# child2.net
KiCad netlist of a schematic drawn in Altium Designer
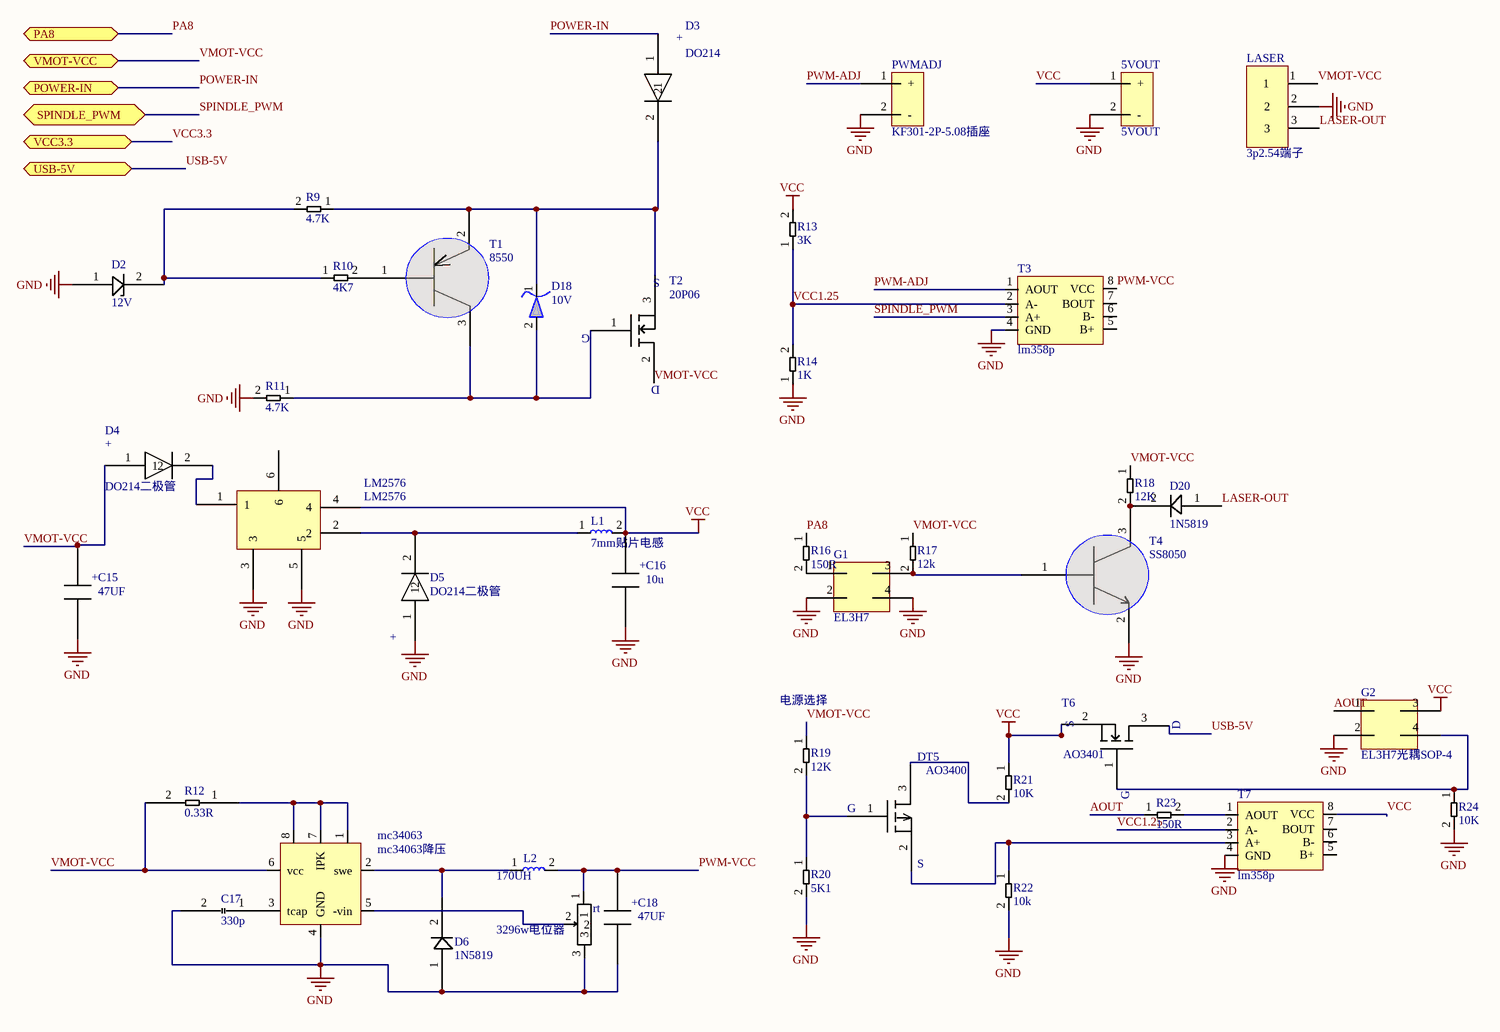
[diagram p0: child2.SchDoc]

(export (version "E")
  (design (tool "Eeschema 10.0.6"))
  (components
    (comp (ref "5VOUT")
      (value "5VOUT")
      (footprint "KF301-2P-5.08插座")
      (libsource (lib "51单片机") (part "KF301-2P-5.08插座"))
    )
    (comp (ref "C15") (value "47UF") (footprint "10u电解电容") (libsource (lib "51单片机") (part "10u电解电容")))
    (comp (ref "C16") (value "10u") (footprint "10u电解电容") (libsource (lib "51单片机") (part "10u电解电容")))
    (comp (ref "C17") (value "330p") (footprint "0805电容") (libsource (lib "51单片机") (part "0805贴片电容")))
    (comp (ref "C18") (value "47UF") (footprint "10u电解电容") (libsource (lib "51单片机") (part "10u电解电容")))
    (comp (ref "D2") (value "12V") (footprint "稳压二极管30v") (libsource (lib "51单片机") (part "稳压二极管")))
    (comp (ref "D3") (value "DO214") (footprint "SMA封装二极管") (libsource (lib "51单片机") (part "DO214二极管")))
    (comp (ref "D4") (value "DO214二极管") (footprint "SMA封装二极管") (libsource (lib "51单片机") (part "DO214二极管")))
    (comp (ref "D5") (value "DO214二极管") (footprint "SMA封装二极管") (libsource (lib "51单片机") (part "DO214二极管")))
    (comp (ref "D6") (value "1N5819") (footprint "0805-二极管") (libsource (lib "51单片机") (part "0805二极管")))
    (comp (ref "D18") (value "10V") (footprint "1/2w贴片稳压二极管") (libsource (lib "51单片机") (part "贴片稳压二极管")))
    (comp (ref "D20") (value "1N5819") (footprint "0805-二极管") (libsource (lib "51单片机") (part "0805二极管")))
    (comp (ref "G1") (value "EL3H7") (footprint "EL3H7SOP-4") (libsource (lib "51单片机") (part "EL3H7光耦SOP-4")))
    (comp (ref "G2")
      (value "EL3H7光耦SOP-4")
      (footprint "EL3H7SOP-4")
      (libsource (lib "51单片机") (part "EL3H7光耦SOP-4"))
    )
    (comp (ref "L1") (value "7mm贴片电感") (footprint "7MM贴片电感") (libsource (lib "51单片机") (part "7mm贴片电感")))
    (comp (ref "L2") (value "170UH") (footprint "7MM贴片电感") (libsource (lib "51单片机") (part "7mm贴片电感")))
    (comp (ref "LASER") (value "3p2.54端子") (footprint "3p2.54端子") (libsource (lib "51单片机") (part "3p2.54端子")))
    (comp (ref "LM2576") (value "LM2576") (footprint "LM2576") (libsource (lib "51单片机") (part "LM2576")))
    (comp (ref "mc34063")
      (value "mc34063降压")
      (footprint "SOP-8")
      (libsource (lib "51单片机") (part "mc34063降压"))
    )
    (comp (ref "PWMADJ")
      (value "KF301-2P-5.08插座")
      (footprint "KF301-2P-5.08插座")
      (libsource (lib "51单片机") (part "KF301-2P-5.08插座"))
    )
    (comp (ref "R9") (value "4.7K") (footprint "0805电阻") (libsource (lib "51单片机") (part "0805贴片电阻")))
    (comp (ref "R10") (value "4K7") (footprint "0805电阻") (libsource (lib "51单片机") (part "0805贴片电阻")))
    (comp (ref "R11") (value "4.7K") (footprint "0805电阻") (libsource (lib "51单片机") (part "0805贴片电阻")))
    (comp (ref "R12") (value "0.33R") (footprint "0805电阻") (libsource (lib "") (part "0805贴片电阻_1")))
    (comp (ref "R13") (value "3K") (footprint "0805电阻") (libsource (lib "51单片机") (part "0805贴片电阻")))
    (comp (ref "R14") (value "1K") (footprint "0805电阻") (libsource (lib "51单片机") (part "0805贴片电阻")))
    (comp (ref "R16") (value "150R") (footprint "0805电阻") (libsource (lib "51单片机") (part "0805贴片电阻")))
    (comp (ref "R17") (value "12k") (footprint "0805电阻") (libsource (lib "51单片机") (part "0805贴片电阻")))
    (comp (ref "R18") (value "12K") (footprint "0805电阻") (libsource (lib "51单片机") (part "0805贴片电阻")))
    (comp (ref "R19") (value "12K") (footprint "0805电阻") (libsource (lib "51单片机") (part "0805贴片电阻")))
    (comp (ref "R20") (value "5K1") (footprint "0805电阻") (libsource (lib "51单片机") (part "0805贴片电阻")))
    (comp (ref "R21") (value "10K") (footprint "0805电阻") (libsource (lib "51单片机") (part "0805贴片电阻")))
    (comp (ref "R22") (value "10k") (footprint "0805电阻") (libsource (lib "51单片机") (part "0805贴片电阻")))
    (comp (ref "R23") (value "150R") (footprint "0805电阻") (libsource (lib "51单片机") (part "0805贴片电阻")))
    (comp (ref "R24") (value "10K") (footprint "0805电阻") (libsource (lib "51单片机") (part "0805贴片电阻")))
    (comp (ref "rt") (value "3296w电位器") (footprint "3296w电位器") (libsource (lib "51单片机") (part "3296w电位器")))
    (comp (ref "T1") (value "8550") (footprint "SOT23") (libsource (lib "51单片机") (part "ss8550三极管")))
    (comp (ref "T2") (value "20P06") (footprint "to-252") (libsource (lib "51单片机") (part "20P06场效应管")))
    (comp (ref "T3") (value "lm358p") (footprint "SOP-8") (libsource (lib "51单片机") (part "lm358p")))
    (comp (ref "T4") (value "SS8050") (footprint "SOT23") (libsource (lib "51单片机") (part "SS8050")))
    (comp (ref "T5") (value "AO3400") (footprint "SOT23") (libsource (lib "51单片机") (part "AO3400")))
    (comp (ref "T6") (value "AO3401") (footprint "SOT23") (libsource (lib "51单片机") (part "AO3401")))
    (comp (ref "T7") (value "lm358p") (footprint "SOP-8") (libsource (lib "51单片机") (part "lm358p")))
  )
  (nets
    (net (code "1") (name "/AOUT") (class "Default")
      (node (ref "G2") (pin "1") (pintype "passive"))
      (node (ref "R23") (pin "1") (pintype "passive"))
    )
    (net (code "2") (name "/LASER-OUT") (class "Default")
      (node (ref "D20") (pin "1") (pintype "passive"))
      (node (ref "LASER") (pin "3") (pinfunction "3_3") (pintype "passive"))
    )
    (net (code "3") (name "/PA8") (class "Default") (node (ref "R16") (pin "1") (pintype "passive")))
    (net (code "4") (name "/POWER-IN") (class "Default")
      (node (ref "D3") (pin "1") (pinfunction "1_1") (pintype "passive"))
    )
    (net (code "5") (name "/PWM-ADJ") (class "Default")
      (node (ref "PWMADJ") (pin "1") (pinfunction "+_1") (pintype "passive"))
      (node (ref "T3") (pin "1") (pinfunction "AOUT_1") (pintype "passive"))
    )
    (net (code "6") (name "/PWM-VCC") (class "Default")
      (node (ref "C18") (pin "1") (pinfunction "1_1") (pintype "passive"))
      (node (ref "L2") (pin "2") (pintype "passive"))
      (node (ref "T3") (pin "8") (pinfunction "VCC_8") (pintype "passive"))
      (node (ref "rt") (pin "1") (pinfunction "1_1") (pintype "passive"))
    )
    (net (code "7") (name "/SPINDLE_PWM") (class "Default")
      (node (ref "T3") (pin "3") (pinfunction "A+_3") (pintype "passive"))
    )
    (net (code "8") (name "/USB-5V") (class "Default") (node (ref "T6") (pin "3") (pintype "passive")))
    (net (code "9") (name "/VCC1.25") (class "Default")
      (node (ref "R13") (pin "1") (pintype "passive"))
      (node (ref "R14") (pin "2") (pintype "passive"))
      (node (ref "T3") (pin "2") (pinfunction "A-_2") (pintype "passive"))
      (node (ref "T7") (pin "2") (pinfunction "A-_2") (pintype "passive"))
    )
    (net (code "11") (name "/VMOT-VCC") (class "Default")
      (node (ref "C15") (pin "1") (pinfunction "1_1") (pintype "passive"))
      (node (ref "D4") (pin "1") (pinfunction "1_1") (pintype "passive"))
      (node (ref "LASER") (pin "1") (pinfunction "1_1") (pintype "passive"))
      (node (ref "R12") (pin "2") (pintype "passive"))
      (node (ref "R17") (pin "1") (pintype "passive"))
      (node (ref "R18") (pin "1") (pintype "passive"))
      (node (ref "R19") (pin "1") (pintype "passive"))
      (node (ref "T2") (pin "2") (pintype "passive"))
      (node (ref "mc34063") (pin "6") (pinfunction "vcc_6") (pintype "passive"))
    )
    (net (code "12") (name "GND") (class "Default")
      (node (ref "5VOUT") (pin "2") (pinfunction "-_2") (pintype "passive"))
      (node (ref "C15") (pin "2") (pinfunction "2_2") (pintype "passive"))
      (node (ref "C16") (pin "2") (pinfunction "2_2") (pintype "passive"))
      (node (ref "C17") (pin "2") (pintype "passive"))
      (node (ref "C18") (pin "2") (pinfunction "2_2") (pintype "passive"))
      (node (ref "D2") (pin "1") (pintype "passive"))
      (node (ref "D5") (pin "1") (pinfunction "1_1") (pintype "passive"))
      (node (ref "D6") (pin "1") (pintype "passive"))
      (node (ref "G1") (pin "2") (pintype "passive"))
      (node (ref "G1") (pin "4") (pintype "passive"))
      (node (ref "G2") (pin "2") (pintype "passive"))
      (node (ref "LASER") (pin "2") (pinfunction "2_2") (pintype "passive"))
      (node (ref "LM2576") (pin "3") (pinfunction "3_3") (pintype "passive"))
      (node (ref "LM2576") (pin "5") (pinfunction "5_5") (pintype "passive"))
      (node (ref "PWMADJ") (pin "2") (pinfunction "-_2") (pintype "passive"))
      (node (ref "R11") (pin "2") (pintype "passive"))
      (node (ref "R14") (pin "1") (pintype "passive"))
      (node (ref "R20") (pin "2") (pintype "passive"))
      (node (ref "R22") (pin "2") (pintype "passive"))
      (node (ref "R24") (pin "2") (pintype "passive"))
      (node (ref "T3") (pin "4") (pinfunction "GND_4") (pintype "passive"))
      (node (ref "T4") (pin "2") (pintype "passive"))
      (node (ref "T7") (pin "4") (pinfunction "GND_4") (pintype "passive"))
      (node (ref "mc34063") (pin "4") (pinfunction "GND_4") (pintype "passive"))
      (node (ref "rt") (pin "3") (pinfunction "3_3") (pintype "passive"))
    )
    (net (code "13") (name "Net-(D2-Pad2)") (class "Default")
      (node (ref "D2") (pin "2") (pintype "passive"))
      (node (ref "R10") (pin "1") (pintype "passive"))
      (node (ref "R9") (pin "2") (pintype "passive"))
    )
    (net (code "14") (name "Net-(D4-Pad2)") (class "Default")
      (node (ref "D4") (pin "2") (pinfunction "2_2") (pintype "passive"))
      (node (ref "LM2576") (pin "1") (pinfunction "1_1") (pintype "passive"))
    )
    (net (code "15") (name "Net-(D5-Pad2)") (class "Default")
      (node (ref "D5") (pin "2") (pinfunction "2_2") (pintype "passive"))
      (node (ref "L1") (pin "1") (pintype "passive"))
      (node (ref "LM2576") (pin "2") (pinfunction "2_2") (pintype "passive"))
    )
    (net (code "16") (name "Net-(D18-Pad1)") (class "Default")
      (node (ref "D18") (pin "1") (pintype "passive"))
      (node (ref "D3") (pin "2") (pinfunction "2_2") (pintype "passive"))
      (node (ref "R9") (pin "1") (pintype "passive"))
      (node (ref "T1") (pin "2") (pintype "passive"))
      (node (ref "T2") (pin "3") (pintype "passive"))
    )
    (net (code "17") (name "Net-(D18-Pad2)") (class "Default")
      (node (ref "D18") (pin "2") (pintype "passive"))
      (node (ref "R11") (pin "1") (pintype "passive"))
      (node (ref "T1") (pin "3") (pintype "passive"))
      (node (ref "T2") (pin "1") (pintype "passive"))
    )
    (net (code "18") (name "Net-(D20-Pad2)") (class "Default")
      (node (ref "D20") (pin "2") (pintype "passive"))
      (node (ref "R18") (pin "2") (pintype "passive"))
      (node (ref "T4") (pin "3") (pintype "passive"))
    )
    (net (code "19") (name "Net-(G1-Pad1)") (class "Default")
      (node (ref "G1") (pin "1") (pintype "passive"))
      (node (ref "R16") (pin "2") (pintype "passive"))
    )
    (net (code "20") (name "Net-(G1-Pad3)") (class "Default")
      (node (ref "G1") (pin "3") (pintype "passive"))
      (node (ref "R17") (pin "2") (pintype "passive"))
      (node (ref "T4") (pin "1") (pintype "passive"))
    )
    (net (code "21") (name "Net-(G2-Pad4)") (class "Default")
      (node (ref "G2") (pin "4") (pintype "passive"))
      (node (ref "R24") (pin "1") (pintype "passive"))
      (node (ref "T6") (pin "1") (pintype "passive"))
    )
    (net (code "22") (name "Net-(R10-Pad2)") (class "Default")
      (node (ref "R10") (pin "2") (pintype "passive"))
      (node (ref "T1") (pin "1") (pintype "passive"))
    )
    (net (code "23") (name "Net-(R19-Pad2)") (class "Default")
      (node (ref "R19") (pin "2") (pintype "passive"))
      (node (ref "R20") (pin "1") (pintype "passive"))
      (node (ref "T5") (pin "1") (pintype "passive"))
    )
    (net (code "24") (name "Net-(R21-Pad2)") (class "Default")
      (node (ref "R21") (pin "2") (pintype "passive"))
      (node (ref "T5") (pin "3") (pintype "passive"))
    )
    (net (code "25") (name "Net-(T7-A+)") (class "Default")
      (node (ref "R22") (pin "1") (pintype "passive"))
      (node (ref "T5") (pin "2") (pintype "passive"))
      (node (ref "T7") (pin "3") (pinfunction "A+_3") (pintype "passive"))
    )
    (net (code "26") (name "Net-(T7-AOUT)") (class "Default")
      (node (ref "R23") (pin "2") (pintype "passive"))
      (node (ref "T7") (pin "1") (pinfunction "AOUT_1") (pintype "passive"))
    )
    (net (code "27") (name "Net-(mc34063--vin)") (class "Default")
      (node (ref "mc34063") (pin "5") (pinfunction "-vin_5") (pintype "passive"))
      (node (ref "rt") (pin "2") (pinfunction "2_2") (pintype "passive"))
    )
    (net (code "28") (name "Net-(mc34063-IPK)") (class "Default")
      (node (ref "R12") (pin "1") (pintype "passive"))
      (node (ref "mc34063") (pin "1") (pintype "passive"))
      (node (ref "mc34063") (pin "7") (pinfunction "IPK_7") (pintype "passive"))
      (node (ref "mc34063") (pin "8") (pintype "passive"))
    )
    (net (code "29") (name "Net-(mc34063-swe)") (class "Default")
      (node (ref "D6") (pin "2") (pintype "passive"))
      (node (ref "L2") (pin "1") (pintype "passive"))
      (node (ref "mc34063") (pin "2") (pinfunction "swe_2") (pintype "passive"))
    )
    (net (code "30") (name "Net-(mc34063-tcap)") (class "Default")
      (node (ref "C17") (pin "1") (pintype "passive"))
      (node (ref "mc34063") (pin "3") (pinfunction "tcap_3") (pintype "passive"))
    )
    (net (code "31") (name "VCC") (class "Default")
      (node (ref "5VOUT") (pin "1") (pinfunction "+_1") (pintype "passive"))
      (node (ref "C16") (pin "1") (pinfunction "1_1") (pintype "passive"))
      (node (ref "G2") (pin "3") (pintype "passive"))
      (node (ref "L1") (pin "2") (pintype "passive"))
      (node (ref "LM2576") (pin "4") (pinfunction "4_4") (pintype "passive"))
      (node (ref "R13") (pin "2") (pintype "passive"))
      (node (ref "R21") (pin "1") (pintype "passive"))
      (node (ref "T6") (pin "2") (pintype "passive"))
      (node (ref "T7") (pin "8") (pinfunction "VCC_8") (pintype "passive"))
    )
    (net (code "32") (name "unconnected-(LM2576-Pad6)") (class "Default")
      (node (ref "LM2576") (pin "6") (pinfunction "6_6") (pintype "passive"))
    )
    (net (code "33") (name "unconnected-(T3-B+-Pad5)") (class "Default")
      (node (ref "T3") (pin "5") (pinfunction "B+_5") (pintype "passive"))
    )
    (net (code "34") (name "unconnected-(T3-B--Pad6)") (class "Default")
      (node (ref "T3") (pin "6") (pinfunction "B-_6") (pintype "passive"))
    )
    (net (code "35") (name "unconnected-(T3-BOUT-Pad7)") (class "Default")
      (node (ref "T3") (pin "7") (pinfunction "BOUT_7") (pintype "passive"))
    )
    (net (code "36") (name "unconnected-(T7-B+-Pad5)") (class "Default")
      (node (ref "T7") (pin "5") (pinfunction "B+_5") (pintype "passive"))
    )
    (net (code "37") (name "unconnected-(T7-B--Pad6)") (class "Default")
      (node (ref "T7") (pin "6") (pinfunction "B-_6") (pintype "passive"))
    )
    (net (code "38") (name "unconnected-(T7-BOUT-Pad7)") (class "Default")
      (node (ref "T7") (pin "7") (pinfunction "BOUT_7") (pintype "passive"))
    )
  )
)
